# Perifericos.net
KiCad netlist of a schematic drawn in Altium Designer
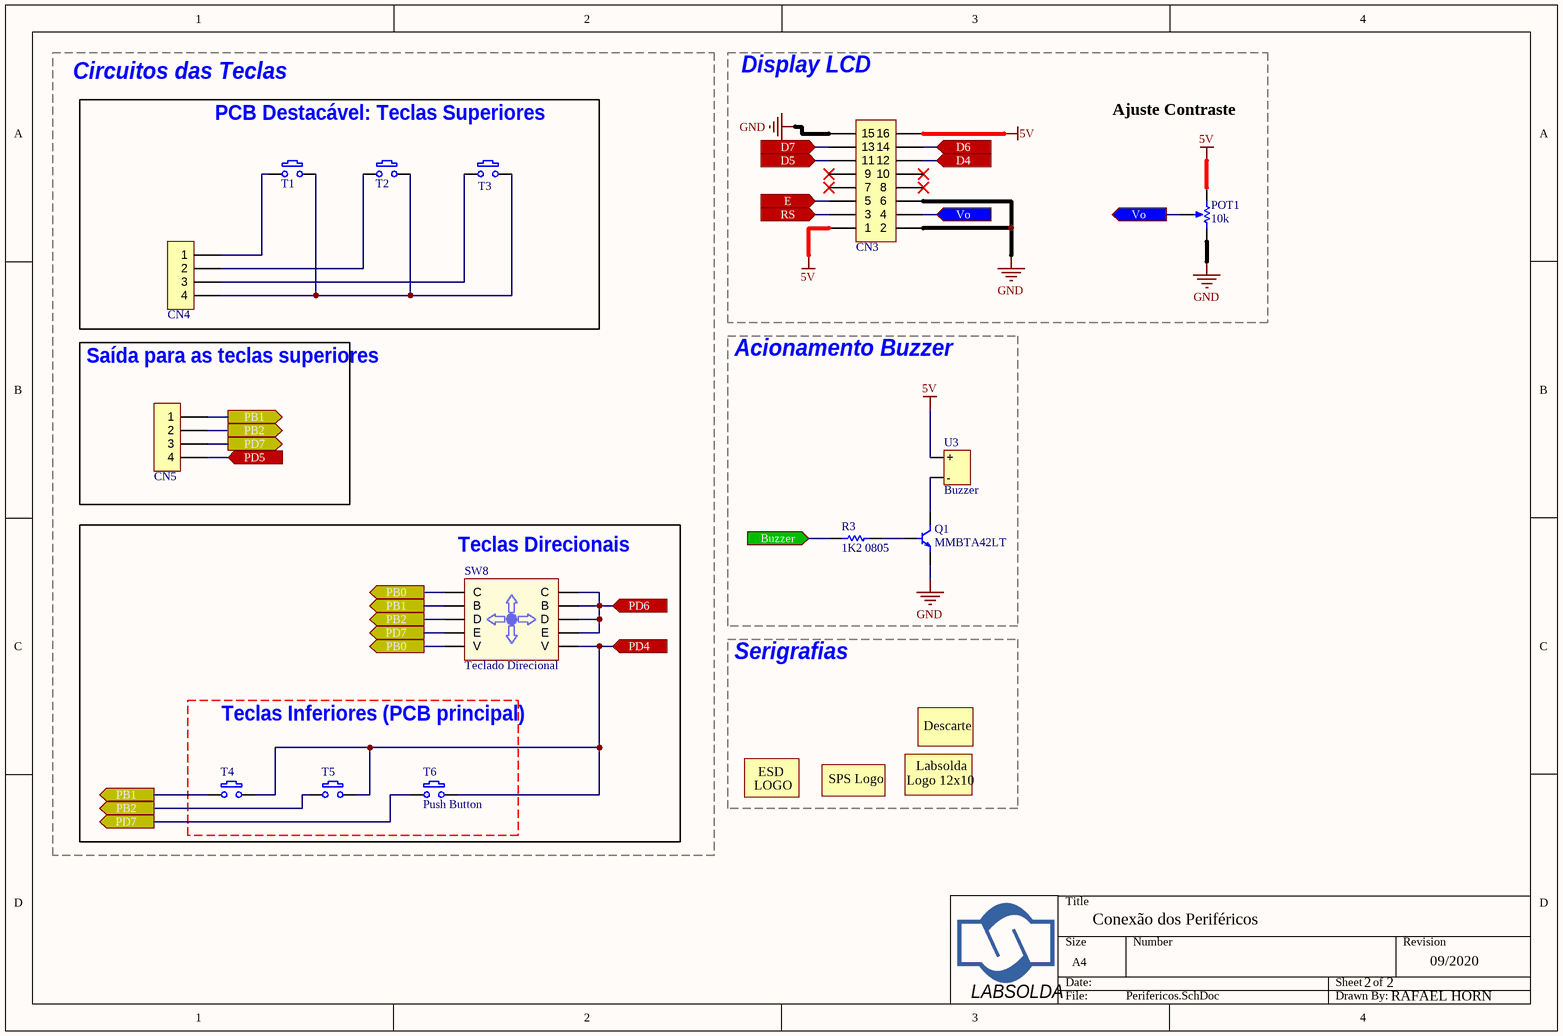
[diagram p0: Perifericos.SchDoc]

(export (version "E")
  (design (tool "Eeschema 10.0.6"))
  (components
    (comp (ref "CN3")
      (value "Header 16 Vias")
      (footprint "Header 16 180º PCI")
      (description "Conector Placa Macho 16 Vias C/ guia 180º 2.54mm")
      (libsource (lib "Conectores") (part "Header 16 180º"))
    )
    (comp (ref "CN4")
      (value "KK 4 Vias")
      (footprint "KK_4W_.100")
      (description "Conector Placa KK 4 Vias 2.54mm")
      (libsource (lib "Conectores") (part "KK 4 Vias"))
    )
    (comp (ref "CN5")
      (value "KK 4 Vias")
      (footprint "KK_4W_.100")
      (description "Conector Placa KK 4 Vias 2.54mm")
      (libsource (lib "Conectores") (part "KK 4 Vias"))
    )
    (comp (ref "Logo1")
      (value "ESD 7x6")
      (footprint "ESD 7x6")
      (libsource (lib "Serigrafias") (part "ESD 7x6"))
    )
    (comp (ref "Logo2") (value "SPS") (footprint "SPS") (libsource (lib "Serigrafias") (part "SPS")))
    (comp (ref "Logo3")
      (value "Labsolda12x10")
      (footprint "LABSOLDA 12x10")
      (libsource (lib "Serigrafias") (part "Labsolda12x10"))
    )
    (comp (ref "Logo4")
      (value "Descarte")
      (footprint "DESCARTE7x7")
      (libsource (lib "Serigrafias") (part "Descarte"))
    )
    (comp (ref "POT1")
      (value "10k")
      (footprint "3386")
      (description "Trimpot Horizontal 3386")
      (libsource (lib "General_Lib") (part "Pot_3386"))
    )
    (comp (ref "Q1")
      (value "MMBTA42LT")
      (footprint "SOT-23")
      (description "High Voltage Transistors NPN Silicon 300V 500mA")
      (libsource (lib "Transistor_SMD") (part "MMBTA42LT"))
    )
    (comp (ref "R3")
      (value "1K2 0805")
      (footprint "0805 - 1K2 1%")
      (description "Resistor SMD 0805 1K2")
      (libsource (lib "Resistor_SMD") (part "1K2 - 0805"))
    )
    (comp (ref "SW8")
      (value "Teclado Direcional")
      (footprint "Teclado_Direcional")
      (description "Teclado Direcional associando botões Multimec")
      (libsource (lib "Contatos") (part "Teclado Direcional"))
    )
    (comp (ref "T1")
      (value "Push Button")
      (footprint "Chave Tactil 6x6x5")
      (description "Chave Tactil 4 terminais 6x6x5mm - KFC-A06")
      (libsource (lib "Contatos") (part "Push Button"))
    )
    (comp (ref "T2")
      (value "Push Button")
      (footprint "Chave Tactil 6x6x5")
      (description "Chave Tactil 4 terminais 6x6x5mm - KFC-A06")
      (libsource (lib "Contatos") (part "Push Button"))
    )
    (comp (ref "T3")
      (value "Push Button")
      (footprint "Chave Tactil 6x6x5")
      (description "Chave Tactil 4 terminais 6x6x5mm - KFC-A06")
      (libsource (lib "Contatos") (part "Push Button"))
    )
    (comp (ref "T4")
      (value "Push Button")
      (footprint "Chave Tactil 6x6x5")
      (description "Chave Tactil 4 terminais 6x6x5mm - KFC-A06")
      (libsource (lib "Contatos") (part "Push Button"))
    )
    (comp (ref "T5")
      (value "Push Button")
      (footprint "Chave Tactil 6x6x5")
      (description "Chave Tactil 4 terminais 6x6x5mm - KFC-A06")
      (libsource (lib "Contatos") (part "Push Button"))
    )
    (comp (ref "T6")
      (value "Push Button")
      (footprint "Chave Tactil 6x6x5")
      (description "Chave Tactil 4 terminais 6x6x5mm - KFC-A06")
      (libsource (lib "Contatos") (part "Push Button"))
    )
    (comp (ref "U3")
      (value "Buzzer")
      (footprint "Buzzer")
      (description "Buzzers Indicator, Internally Driven Magnetic 5V 30mA 2.73kHz 82dB @ 5V, 10cm Through Hole PC Pins")
      (fields (field (name "PARTNUMBER") "AI-1027-TWT-5V-2-R"))
      (libsource (lib "Modulos") (part "Buzzer 5V"))
    )
  )
  (nets
    (net (code "1") (name "/Buzzer") (class "Default")
      (node (ref "R3") (pin "1") (pinfunction "1_1") (pintype "passive"))
    )
    (net (code "2") (name "/D4") (class "Default")
      (node (ref "CN3") (pin "12") (pinfunction "12_12") (pintype "passive"))
    )
    (net (code "3") (name "/D5") (class "Default")
      (node (ref "CN3") (pin "11") (pinfunction "11_11") (pintype "passive"))
    )
    (net (code "4") (name "/D6") (class "Default")
      (node (ref "CN3") (pin "14") (pinfunction "14_14") (pintype "passive"))
    )
    (net (code "5") (name "/D7") (class "Default")
      (node (ref "CN3") (pin "13") (pinfunction "13_13") (pintype "passive"))
    )
    (net (code "6") (name "/E") (class "Default")
      (node (ref "CN3") (pin "5") (pinfunction "5_5") (pintype "passive"))
    )
    (net (code "7") (name "/PB0") (class "Default")
      (node (ref "SW8") (pin "1") (pinfunction "C_1") (pintype "passive"))
      (node (ref "SW8") (pin "9") (pinfunction "V_9") (pintype "passive"))
    )
    (net (code "8") (name "/PB1") (class "Default")
      (node (ref "CN5") (pin "1") (pinfunction "1_1") (pintype "passive"))
      (node (ref "SW8") (pin "3") (pinfunction "B_3") (pintype "passive"))
      (node (ref "T4") (pin "1") (pinfunction "1_1") (pintype "passive"))
    )
    (net (code "9") (name "/PB2") (class "Default")
      (node (ref "CN5") (pin "2") (pinfunction "2_2") (pintype "passive"))
      (node (ref "SW8") (pin "5") (pinfunction "D_5") (pintype "passive"))
      (node (ref "T5") (pin "1") (pinfunction "1_1") (pintype "passive"))
    )
    (net (code "10") (name "/PD4") (class "Default")
      (node (ref "SW8") (pin "10") (pinfunction "V_10") (pintype "passive"))
      (node (ref "T4") (pin "2") (pinfunction "2_2") (pintype "passive"))
      (node (ref "T5") (pin "2") (pinfunction "2_2") (pintype "passive"))
      (node (ref "T6") (pin "2") (pinfunction "2_2") (pintype "passive"))
    )
    (net (code "11") (name "/PD5") (class "Default")
      (node (ref "CN5") (pin "4") (pinfunction "4_4") (pintype "passive"))
    )
    (net (code "12") (name "/PD6") (class "Default")
      (node (ref "SW8") (pin "2") (pinfunction "C_2") (pintype "passive"))
      (node (ref "SW8") (pin "4") (pinfunction "B_4") (pintype "passive"))
      (node (ref "SW8") (pin "6") (pinfunction "D_6") (pintype "passive"))
      (node (ref "SW8") (pin "8") (pinfunction "E_8") (pintype "passive"))
    )
    (net (code "13") (name "/PD7") (class "Default")
      (node (ref "CN5") (pin "3") (pinfunction "3_3") (pintype "passive"))
      (node (ref "SW8") (pin "7") (pinfunction "E_7") (pintype "passive"))
      (node (ref "T6") (pin "1") (pinfunction "1_1") (pintype "passive"))
    )
    (net (code "14") (name "/RS") (class "Default")
      (node (ref "CN3") (pin "3") (pinfunction "3_3") (pintype "passive"))
    )
    (net (code "15") (name "/Vo") (class "Default")
      (node (ref "CN3") (pin "4") (pinfunction "4_4") (pintype "passive"))
      (node (ref "POT1") (pin "3") (pinfunction "TAP_3") (pintype "passive"))
    )
    (net (code "16") (name "5V") (class "Default")
      (node (ref "CN3") (pin "1") (pinfunction "1_1") (pintype "passive"))
      (node (ref "CN3") (pin "16") (pinfunction "16_16") (pintype "passive"))
      (node (ref "POT1") (pin "1") (pinfunction "TOP_1") (pintype "passive"))
      (node (ref "U3") (pin "1") (pinfunction "+_1") (pintype "passive"))
    )
    (net (code "17") (name "GND") (class "Default")
      (node (ref "CN3") (pin "15") (pinfunction "15_15") (pintype "passive"))
      (node (ref "CN3") (pin "2") (pinfunction "2_2") (pintype "passive"))
      (node (ref "CN3") (pin "6") (pinfunction "6_6") (pintype "passive"))
      (node (ref "POT1") (pin "2") (pinfunction "BOT_2") (pintype "passive"))
      (node (ref "Q1") (pin "E") (pinfunction "E_E") (pintype "passive"))
    )
    (net (code "18") (name "Net-(CN4-Pad1)") (class "Default")
      (node (ref "CN4") (pin "1") (pinfunction "1_1") (pintype "passive"))
      (node (ref "T1") (pin "2") (pinfunction "2_2") (pintype "passive"))
    )
    (net (code "19") (name "Net-(CN4-Pad2)") (class "Default")
      (node (ref "CN4") (pin "2") (pinfunction "2_2") (pintype "passive"))
      (node (ref "T2") (pin "2") (pinfunction "2_2") (pintype "passive"))
    )
    (net (code "20") (name "Net-(CN4-Pad3)") (class "Default")
      (node (ref "CN4") (pin "3") (pinfunction "3_3") (pintype "passive"))
      (node (ref "T3") (pin "1") (pinfunction "1_1") (pintype "passive"))
    )
    (net (code "21") (name "Net-(CN4-Pad4)") (class "Default")
      (node (ref "CN4") (pin "4") (pinfunction "4_4") (pintype "passive"))
      (node (ref "T1") (pin "1") (pinfunction "1_1") (pintype "passive"))
      (node (ref "T2") (pin "1") (pinfunction "1_1") (pintype "passive"))
      (node (ref "T3") (pin "2") (pinfunction "2_2") (pintype "passive"))
    )
    (net (code "22") (name "Net-(Q1-PadB)") (class "Default")
      (node (ref "Q1") (pin "B") (pinfunction "B_B") (pintype "passive"))
      (node (ref "R3") (pin "2") (pinfunction "2_2") (pintype "passive"))
    )
    (net (code "23") (name "Net-(U3--)") (class "Default")
      (node (ref "Q1") (pin "C") (pinfunction "C_C") (pintype "passive"))
      (node (ref "U3") (pin "2") (pinfunction "-_2") (pintype "passive"))
    )
    (net (code "24") (name "unconnected-(CN3-Pad7)") (class "Default")
      (node (ref "CN3") (pin "7") (pinfunction "7_7") (pintype "passive+no_connect"))
    )
    (net (code "25") (name "unconnected-(CN3-Pad8)") (class "Default")
      (node (ref "CN3") (pin "8") (pinfunction "8_8") (pintype "passive+no_connect"))
    )
    (net (code "26") (name "unconnected-(CN3-Pad9)") (class "Default")
      (node (ref "CN3") (pin "9") (pinfunction "9_9") (pintype "passive+no_connect"))
    )
    (net (code "27") (name "unconnected-(CN3-Pad10)") (class "Default")
      (node (ref "CN3") (pin "10") (pinfunction "10_10") (pintype "passive+no_connect"))
    )
  )
)
